# TCP_CONNECTOR.net
KiCad netlist of a schematic drawn in Altium Designer
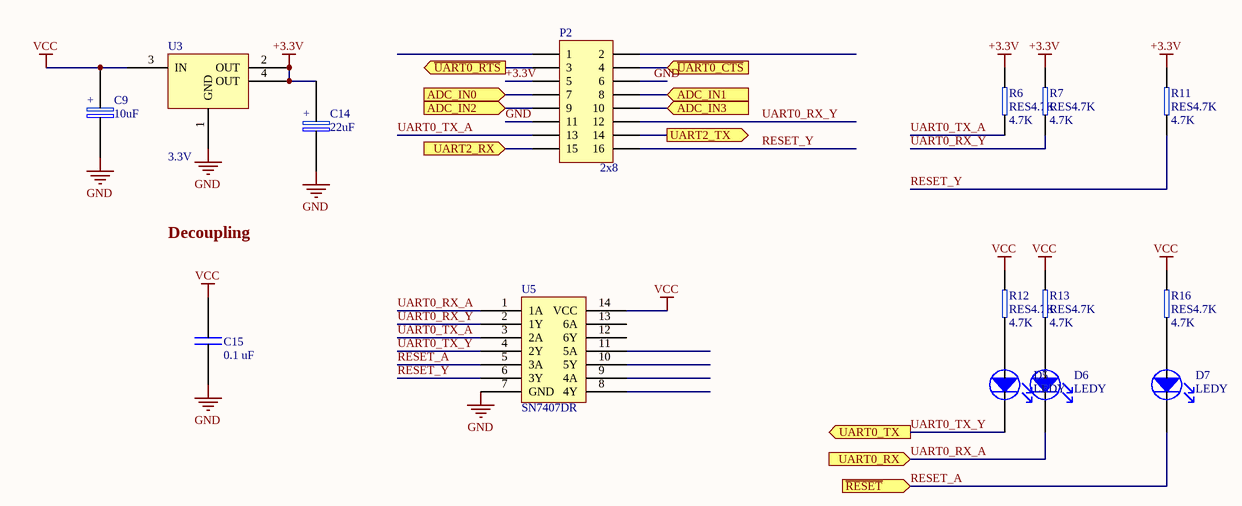
[diagram p0: TCP_CONNECTOR.SchDoc]

(export (version "E")
  (design (tool "Eeschema 10.0.6"))
  (components
    (comp (ref "C9")
      (value "10uF")
      (footprint "CAP0805")
      (description "Capacitores cerámicos de capas múltiples (MLCC) - SMD/SMT 0805 10uF 16volts X5R 10%")
      (fields (field (name "MPN") "GRM21BR61C106KE15L") (field (name "Comment") "CAP10uF"))
      (libsource (lib "Miscellaneous Devices") (part "CAP10uF"))
    )
    (comp (ref "C14")
      (value "22uF")
      (footprint "CAP0805")
      (description "Capacitores cerámicos de capas múltiples (MLCC) - SMD/SMT 0805 22uF 16volts X5R 20%")
      (fields (field (name "MPN") "GRM21BR61C226ME44L") (field (name "Comment") "CAP22uF"))
      (libsource (lib "Miscellaneous Devices") (part "CAP22uF"))
    )
    (comp (ref "C15")
      (value "0.1 uF")
      (footprint "techdev:CAP0603")
      (description "Capacitores cerámicos de capas múltiples (MLCC) - SMD/SMT 0603 0.1uF 16volts X7R 5%")
      (fields (field (name "MPN") "VJ0603Y104JXJPW1BC") (field (name "Comment") "CAP0.1uF"))
      (libsource (lib "Miscellaneous Devices") (part "C0.1UF"))
    )
    (comp (ref "D5")
      (value "LEDY")
      (footprint "150060YS75000")
      (description "LED estándar - SMD (montaje superficial) WL-SMCW SMDMono TpVw Waterclr 0603 Yellow")
      (fields (field (name "MPN") "150060YS75000"))
      (libsource (lib "techdev") (part "LEDY"))
    )
    (comp (ref "D6")
      (value "LEDY")
      (footprint "150060YS75000")
      (description "LED estándar - SMD (montaje superficial) WL-SMCW SMDMono TpVw Waterclr 0603 Yellow")
      (fields (field (name "MPN") "150060YS75000"))
      (libsource (lib "techdev") (part "LEDY"))
    )
    (comp (ref "D7")
      (value "LEDY")
      (footprint "150060YS75000")
      (description "LED estándar - SMD (montaje superficial) WL-SMCW SMDMono TpVw Waterclr 0603 Yellow")
      (fields (field (name "MPN") "150060YS75000"))
      (libsource (lib "techdev") (part "LEDY"))
    )
    (comp (ref "P2")
      (value "2x8")
      (footprint "HDR2X8")
      (description "Alojamientos de cables y cabecera 2X08 POS VERT TIN")
      (fields (field (name "MPN") "826925-8"))
      (libsource (lib "Miscellaneous Connectors") (part "Header 8X2"))
    )
    (comp (ref "R6")
      (value "RES4.7K")
      (footprint "RES0603")
      (description "Resistores de película gruesa - SMD 1/10watt 4.7Kohms 1%")
      (fields (field (name "MPN") "CRCW06034K70FKEA") (field (name "ALTIUM_VALUE") "4.7K"))
      (libsource (lib "Miscellaneous Devices") (part "RES4.7K"))
    )
    (comp (ref "R7")
      (value "RES4.7K")
      (footprint "RES0603")
      (description "Resistores de película gruesa - SMD 1/10watt 4.7Kohms 1%")
      (fields (field (name "MPN") "CRCW06034K70FKEA") (field (name "ALTIUM_VALUE") "4.7K"))
      (libsource (lib "Miscellaneous Devices") (part "RES4.7K"))
    )
    (comp (ref "R11")
      (value "RES4.7K")
      (footprint "RES0603")
      (description "Resistores de película gruesa - SMD 1/10watt 4.7Kohms 1%")
      (fields (field (name "MPN") "CRCW06034K70FKEA") (field (name "ALTIUM_VALUE") "4.7K"))
      (libsource (lib "Miscellaneous Devices") (part "RES4.7K"))
    )
    (comp (ref "R12")
      (value "RES4.7K")
      (footprint "RES0603")
      (description "Resistores de película gruesa - SMD 1/10watt 4.7Kohms 1%")
      (fields (field (name "MPN") "CRCW06034K70FKEA") (field (name "ALTIUM_VALUE") "4.7K"))
      (libsource (lib "Miscellaneous Devices") (part "RES4.7K"))
    )
    (comp (ref "R13")
      (value "RES4.7K")
      (footprint "RES0603")
      (description "Resistores de película gruesa - SMD 1/10watt 4.7Kohms 1%")
      (fields (field (name "MPN") "CRCW06034K70FKEA") (field (name "ALTIUM_VALUE") "4.7K"))
      (libsource (lib "Miscellaneous Devices") (part "RES4.7K"))
    )
    (comp (ref "R16")
      (value "RES4.7K")
      (footprint "RES0603")
      (description "Resistores de película gruesa - SMD 1/10watt 4.7Kohms 1%")
      (fields (field (name "MPN") "CRCW06034K70FKEA") (field (name "ALTIUM_VALUE") "4.7K"))
      (libsource (lib "Miscellaneous Devices") (part "RES4.7K"))
    )
    (comp (ref "U3")
      (value "3.3V")
      (footprint "AZ1117H-3.3TRE1")
      (description "Reguladores de tensión lineal LDO BJT HiCurr 1.15V at 1A")
      (fields (field (name "MPN") "AZ1117H-3.3TRE1"))
      (libsource (lib "Miscellaneous Devices") (part "AZ1117H-3.3TRE1"))
    )
    (comp (ref "U5")
      (value "SN7407DR")
      (footprint "SOIC14")
      (description "Búfers y controladores de línea Hex Buffer/Driver")
      (libsource (lib "techdev") (part "SN7407DR"))
    )
  )
  (nets
    (net (code "1") (name "+3.3V") (class "Default")
      (node (ref "C14") (pin "1") (pinfunction "pos_1") (pintype "passive"))
      (node (ref "P2") (pin "5") (pinfunction "5_5") (pintype "passive"))
      (node (ref "R11") (pin "1") (pinfunction "pos_1") (pintype "passive"))
      (node (ref "R6") (pin "1") (pinfunction "pos_1") (pintype "passive"))
      (node (ref "R7") (pin "1") (pinfunction "pos_1") (pintype "passive"))
      (node (ref "U3") (pin "2") (pinfunction "OUT_2") (pintype "passive"))
      (node (ref "U3") (pin "4") (pinfunction "OUT_4") (pintype "passive"))
    )
    (net (code "2") (name "/ADC_IN0") (class "Default")
      (node (ref "P2") (pin "7") (pinfunction "7_7") (pintype "passive"))
    )
    (net (code "3") (name "/ADC_IN1") (class "Default")
      (node (ref "P2") (pin "8") (pinfunction "8_8") (pintype "passive"))
    )
    (net (code "4") (name "/ADC_IN2") (class "Default")
      (node (ref "P2") (pin "9") (pinfunction "9_9") (pintype "passive"))
    )
    (net (code "5") (name "/ADC_IN3") (class "Default")
      (node (ref "P2") (pin "10") (pinfunction "10_10") (pintype "passive"))
    )
    (net (code "7") (name "/RESET_A") (class "Default")
      (node (ref "D7") (pin "1") (pinfunction "Cathode_1") (pintype "passive"))
      (node (ref "U5") (pin "5") (pinfunction "3A_5") (pintype "passive"))
    )
    (net (code "8") (name "/RESET_Y") (class "Default")
      (node (ref "P2") (pin "16") (pinfunction "16_16") (pintype "passive"))
      (node (ref "R11") (pin "2") (pinfunction "neg_2") (pintype "passive"))
      (node (ref "U5") (pin "6") (pinfunction "3Y_6") (pintype "passive"))
    )
    (net (code "9") (name "/UART0_RX_A") (class "Default")
      (node (ref "D6") (pin "1") (pinfunction "Cathode_1") (pintype "passive"))
      (node (ref "U5") (pin "1") (pinfunction "1A_1") (pintype "passive"))
    )
    (net (code "10") (name "/UART0_RX_Y") (class "Default")
      (node (ref "P2") (pin "12") (pinfunction "12_12") (pintype "passive"))
      (node (ref "R7") (pin "2") (pinfunction "neg_2") (pintype "passive"))
      (node (ref "U5") (pin "2") (pinfunction "1Y_2") (pintype "passive"))
    )
    (net (code "11") (name "/UART0_TX_A") (class "Default")
      (node (ref "P2") (pin "13") (pinfunction "13_13") (pintype "passive"))
      (node (ref "R6") (pin "2") (pinfunction "neg_2") (pintype "passive"))
      (node (ref "U5") (pin "3") (pinfunction "2A_3") (pintype "passive"))
    )
    (net (code "12") (name "/UART0_TX_Y") (class "Default")
      (node (ref "D5") (pin "1") (pinfunction "Cathode_1") (pintype "passive"))
      (node (ref "U5") (pin "4") (pinfunction "2Y_4") (pintype "passive"))
    )
    (net (code "13") (name "/UART2_RX") (class "Default")
      (node (ref "P2") (pin "15") (pinfunction "15_15") (pintype "passive"))
    )
    (net (code "14") (name "/UART2_TX") (class "Default")
      (node (ref "P2") (pin "14") (pinfunction "14_14") (pintype "passive"))
    )
    (net (code "15") (name "/~{UART0_CTS}") (class "Default")
      (node (ref "P2") (pin "4") (pinfunction "4_4") (pintype "passive"))
    )
    (net (code "16") (name "/~{UART0_RTS}") (class "Default")
      (node (ref "P2") (pin "3") (pinfunction "3_3") (pintype "passive"))
    )
    (net (code "17") (name "GND") (class "Default")
      (node (ref "C14") (pin "2") (pinfunction "neg_2") (pintype "passive"))
      (node (ref "C15") (pin "2") (pintype "passive"))
      (node (ref "C9") (pin "2") (pinfunction "neg_2") (pintype "passive"))
      (node (ref "P2") (pin "11") (pinfunction "11_11") (pintype "passive"))
      (node (ref "P2") (pin "6") (pinfunction "6_6") (pintype "passive"))
      (node (ref "U3") (pin "1") (pinfunction "GND_1") (pintype "passive"))
      (node (ref "U5") (pin "7") (pinfunction "GND_7") (pintype "passive"))
    )
    (net (code "18") (name "Net-(D5-Anode)") (class "Default")
      (node (ref "D5") (pin "2") (pinfunction "Anode_2") (pintype "passive"))
      (node (ref "R12") (pin "2") (pinfunction "neg_2") (pintype "passive"))
    )
    (net (code "19") (name "Net-(D6-Anode)") (class "Default")
      (node (ref "D6") (pin "2") (pinfunction "Anode_2") (pintype "passive"))
      (node (ref "R13") (pin "2") (pinfunction "neg_2") (pintype "passive"))
    )
    (net (code "20") (name "Net-(D7-Anode)") (class "Default")
      (node (ref "D7") (pin "2") (pinfunction "Anode_2") (pintype "passive"))
      (node (ref "R16") (pin "2") (pinfunction "neg_2") (pintype "passive"))
    )
    (net (code "21") (name "VCC") (class "Default")
      (node (ref "C15") (pin "1") (pintype "passive"))
      (node (ref "C9") (pin "1") (pinfunction "pos_1") (pintype "passive"))
      (node (ref "R12") (pin "1") (pinfunction "pos_1") (pintype "passive"))
      (node (ref "R13") (pin "1") (pinfunction "pos_1") (pintype "passive"))
      (node (ref "R16") (pin "1") (pinfunction "pos_1") (pintype "passive"))
      (node (ref "U3") (pin "3") (pinfunction "IN_3") (pintype "passive"))
      (node (ref "U5") (pin "14") (pinfunction "VCC_14") (pintype "passive"))
    )
    (net (code "22") (name "unconnected-(P2-Pad1)") (class "Default")
      (node (ref "P2") (pin "1") (pinfunction "1_1") (pintype "passive"))
    )
    (net (code "23") (name "unconnected-(P2-Pad2)") (class "Default")
      (node (ref "P2") (pin "2") (pinfunction "2_2") (pintype "passive"))
    )
    (net (code "24") (name "unconnected-(U5-4A-Pad9)") (class "Default")
      (node (ref "U5") (pin "9") (pinfunction "4A_9") (pintype "passive"))
    )
    (net (code "25") (name "unconnected-(U5-4Y-Pad8)") (class "Default")
      (node (ref "U5") (pin "8") (pinfunction "4Y_8") (pintype "passive"))
    )
    (net (code "26") (name "unconnected-(U5-5A-Pad11)") (class "Default")
      (node (ref "U5") (pin "11") (pinfunction "5A_11") (pintype "passive"))
    )
    (net (code "27") (name "unconnected-(U5-5Y-Pad10)") (class "Default")
      (node (ref "U5") (pin "10") (pinfunction "5Y_10") (pintype "passive"))
    )
    (net (code "28") (name "unconnected-(U5-6A-Pad13)") (class "Default")
      (node (ref "U5") (pin "13") (pinfunction "6A_13") (pintype "passive"))
    )
    (net (code "29") (name "unconnected-(U5-6Y-Pad12)") (class "Default")
      (node (ref "U5") (pin "12") (pinfunction "6Y_12") (pintype "passive"))
    )
  )
)
